# gamepad.net
KiCad netlist of a schematic drawn in EasyEDA Pro
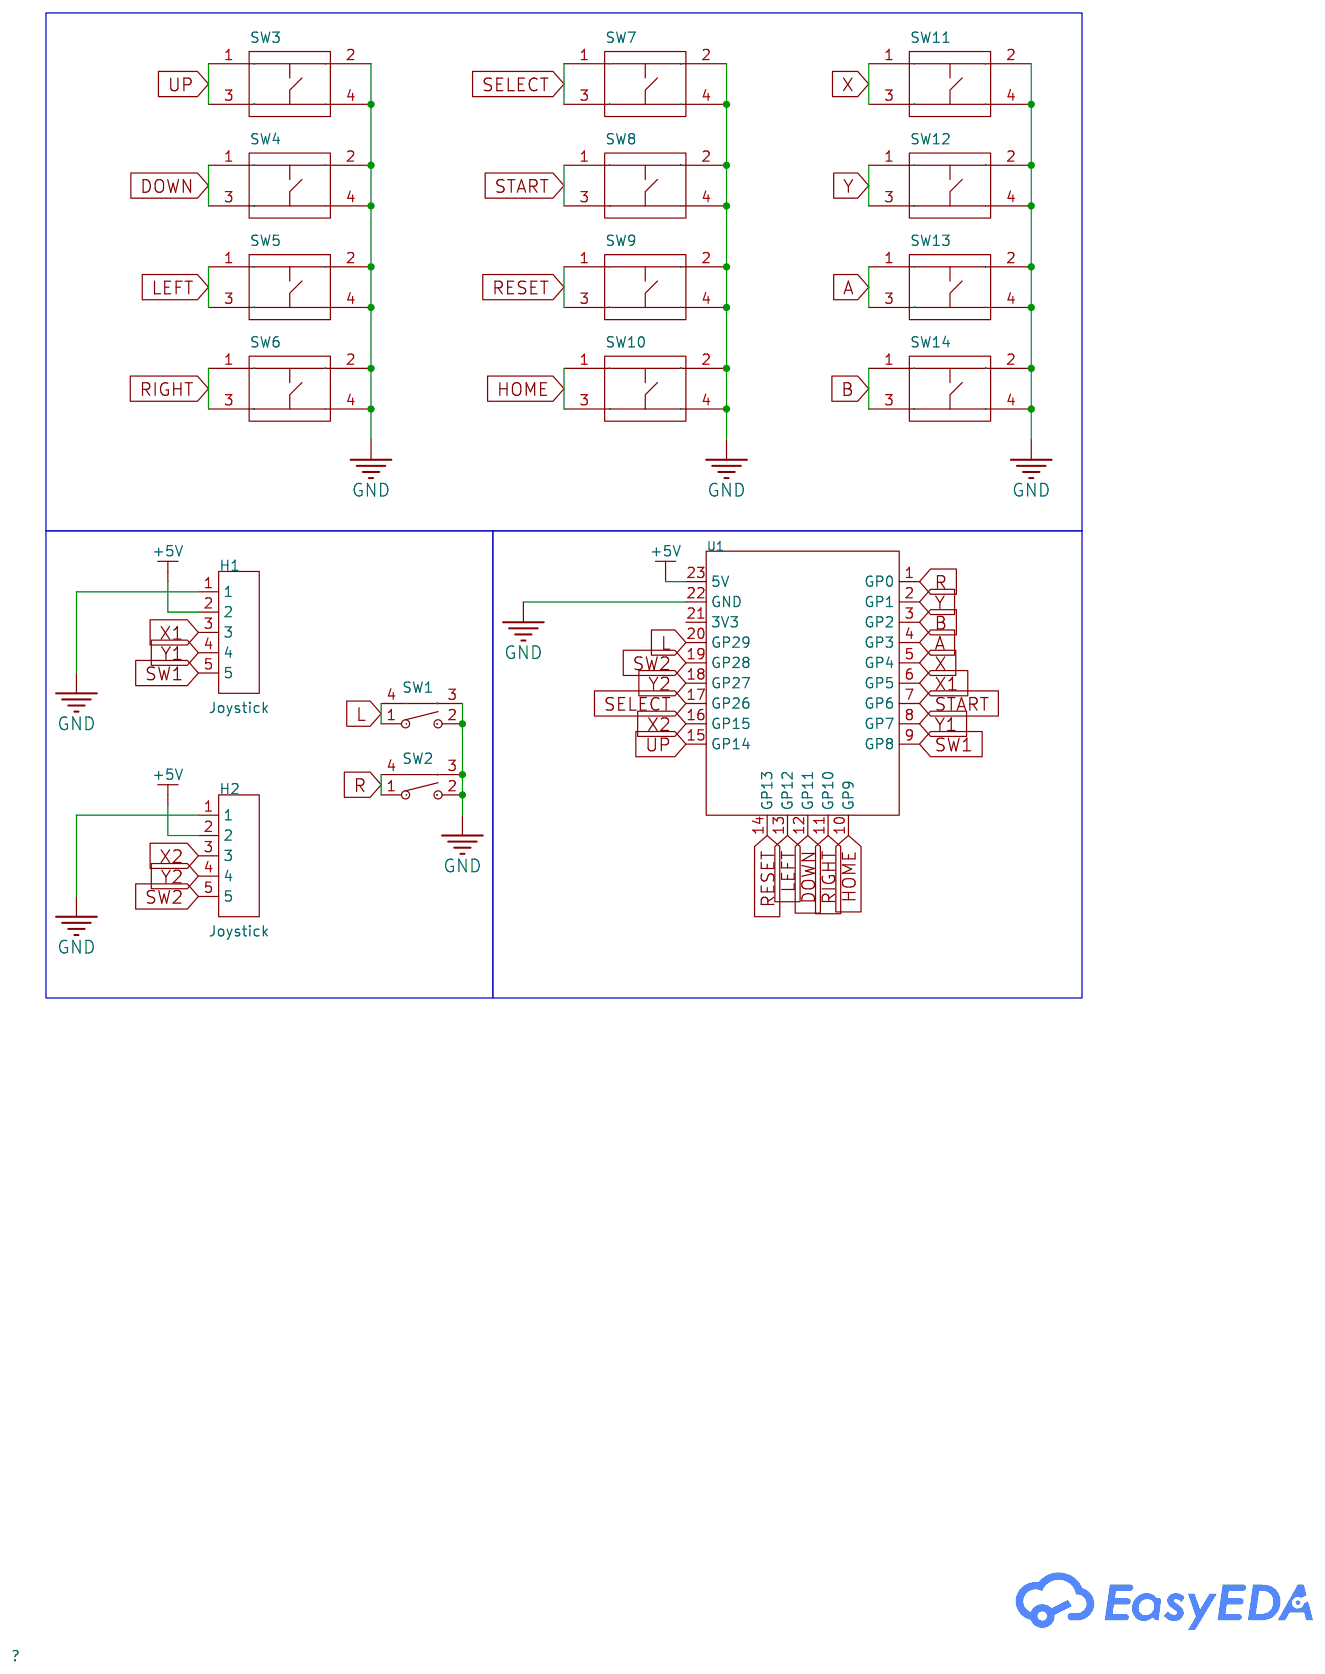
[diagram p0: schematic sheet]

(export (version "E")
  (design (tool "Eeschema 10.0.6"))
  (components
    (comp (ref "H1")
      (value "Joystick")
      (footprint "easyedapro:HDR-TH_5P-P2.54_HTSW-105-08-F-S")
      (fields (field (name "Manufacturer") "SAMTEC"))
      (libsource (lib "easyedapro") (part "MTSW-105-22-F-S-370"))
    )
    (comp (ref "H2")
      (value "Joystick")
      (footprint "easyedapro:HDR-TH_5P-P2.54_HTSW-105-08-F-S")
      (fields (field (name "Manufacturer") "SAMTEC"))
      (libsource (lib "easyedapro") (part "MTSW-105-22-F-S-370"))
    )
    (comp (ref "SW1")
      (value "K2-1102AQ-H4CW-01")
      (footprint "easyedapro:SW-TH_K2-1102BQ-G4CW-01")
      (fields (field (name "Manufacturer") "韩国韩荣"))
      (libsource (lib "easyedapro") (part "K2-1102AQ-H4CW-01"))
    )
    (comp (ref "SW2")
      (value "K2-1102AQ-H4CW-01")
      (footprint "easyedapro:SW-TH_K2-1102BQ-G4CW-01")
      (fields (field (name "Manufacturer") "韩国韩荣"))
      (libsource (lib "easyedapro") (part "K2-1102AQ-H4CW-01"))
    )
    (comp (ref "SW3")
      (value "K2-1102DP-C4SW-04")
      (footprint "easyedapro:KEY-TH_4P-L6.0-W6.0-P4.50-LS6.50")
      (fields (field (name "Manufacturer") "韩国韩荣"))
      (libsource (lib "easyedapro") (part "K2-1102DP-C4SW-04"))
    )
    (comp (ref "SW4")
      (value "K2-1102DP-C4SW-04")
      (footprint "easyedapro:KEY-TH_4P-L6.0-W6.0-P4.50-LS6.50")
      (fields (field (name "Manufacturer") "韩国韩荣"))
      (libsource (lib "easyedapro") (part "K2-1102DP-C4SW-04"))
    )
    (comp (ref "SW5")
      (value "K2-1102DP-C4SW-04")
      (footprint "easyedapro:KEY-TH_4P-L6.0-W6.0-P4.50-LS6.50")
      (fields (field (name "Manufacturer") "韩国韩荣"))
      (libsource (lib "easyedapro") (part "K2-1102DP-C4SW-04"))
    )
    (comp (ref "SW6")
      (value "K2-1102DP-C4SW-04")
      (footprint "easyedapro:KEY-TH_4P-L6.0-W6.0-P4.50-LS6.50")
      (fields (field (name "Manufacturer") "韩国韩荣"))
      (libsource (lib "easyedapro") (part "K2-1102DP-C4SW-04"))
    )
    (comp (ref "SW7")
      (value "K2-1102DP-C4SW-04")
      (footprint "easyedapro:KEY-TH_4P-L6.0-W6.0-P4.50-LS6.50")
      (fields (field (name "Manufacturer") "韩国韩荣"))
      (libsource (lib "easyedapro") (part "K2-1102DP-C4SW-04"))
    )
    (comp (ref "SW8")
      (value "K2-1102DP-C4SW-04")
      (footprint "easyedapro:KEY-TH_4P-L6.0-W6.0-P4.50-LS6.50")
      (fields (field (name "Manufacturer") "韩国韩荣"))
      (libsource (lib "easyedapro") (part "K2-1102DP-C4SW-04"))
    )
    (comp (ref "SW9")
      (value "K2-1102DP-C4SW-04")
      (footprint "easyedapro:KEY-TH_4P-L6.0-W6.0-P4.50-LS6.50")
      (fields (field (name "Manufacturer") "韩国韩荣"))
      (libsource (lib "easyedapro") (part "K2-1102DP-C4SW-04"))
    )
    (comp (ref "SW10")
      (value "K2-1102DP-C4SW-04")
      (footprint "easyedapro:KEY-TH_4P-L6.0-W6.0-P4.50-LS6.50")
      (fields (field (name "Manufacturer") "韩国韩荣"))
      (libsource (lib "easyedapro") (part "K2-1102DP-C4SW-04"))
    )
    (comp (ref "SW11")
      (value "K2-1102DP-C4SW-04")
      (footprint "easyedapro:KEY-TH_4P-L6.0-W6.0-P4.50-LS6.50")
      (fields (field (name "Manufacturer") "韩国韩荣"))
      (libsource (lib "easyedapro") (part "K2-1102DP-C4SW-04"))
    )
    (comp (ref "SW12")
      (value "K2-1102DP-C4SW-04")
      (footprint "easyedapro:KEY-TH_4P-L6.0-W6.0-P4.50-LS6.50")
      (fields (field (name "Manufacturer") "韩国韩荣"))
      (libsource (lib "easyedapro") (part "K2-1102DP-C4SW-04"))
    )
    (comp (ref "SW13")
      (value "K2-1102DP-C4SW-04")
      (footprint "easyedapro:KEY-TH_4P-L6.0-W6.0-P4.50-LS6.50")
      (fields (field (name "Manufacturer") "韩国韩荣"))
      (libsource (lib "easyedapro") (part "K2-1102DP-C4SW-04"))
    )
    (comp (ref "SW14")
      (value "K2-1102DP-C4SW-04")
      (footprint "easyedapro:KEY-TH_4P-L6.0-W6.0-P4.50-LS6.50")
      (fields (field (name "Manufacturer") "韩国韩荣"))
      (libsource (lib "easyedapro") (part "K2-1102DP-C4SW-04"))
    )
    (comp (ref "U1")
      (value "RP2040-Zero")
      (footprint "easyedapro:RP2040_Zero")
      (fields (field (name "Manufacturer") "Waveshare(微雪电子)"))
      (libsource (lib "easyedapro") (part "RP2040-ZERO"))
    )
  )
  (nets
    (net (code "1") (name "+5V") (class "Default")
      (node (ref "H1") (pin "2") (pinfunction "2_2") (pintype "unspecified"))
      (node (ref "H2") (pin "2") (pinfunction "2_2") (pintype "unspecified"))
      (node (ref "U1") (pin "23") (pinfunction "5V_23") (pintype "input"))
    )
    (net (code "2") (name "A") (class "Default")
      (node (ref "SW13") (pin "1") (pinfunction "1_1") (pintype "unspecified"))
      (node (ref "SW13") (pin "3") (pinfunction "3_3") (pintype "unspecified"))
      (node (ref "U1") (pin "4") (pinfunction "GP3_4") (pintype "input"))
    )
    (net (code "3") (name "B") (class "Default")
      (node (ref "SW14") (pin "1") (pinfunction "1_1") (pintype "unspecified"))
      (node (ref "SW14") (pin "3") (pinfunction "3_3") (pintype "unspecified"))
      (node (ref "U1") (pin "3") (pinfunction "GP2_3") (pintype "input"))
    )
    (net (code "4") (name "DOWN") (class "Default")
      (node (ref "SW4") (pin "1") (pinfunction "1_1") (pintype "unspecified"))
      (node (ref "SW4") (pin "3") (pinfunction "3_3") (pintype "unspecified"))
      (node (ref "U1") (pin "12") (pinfunction "GP11_12") (pintype "input"))
    )
    (net (code "5") (name "GND") (class "Default")
      (node (ref "H1") (pin "1") (pinfunction "1_1") (pintype "unspecified"))
      (node (ref "H2") (pin "1") (pinfunction "1_1") (pintype "unspecified"))
      (node (ref "SW1") (pin "2") (pinfunction "2_2") (pintype "input"))
      (node (ref "SW1") (pin "3") (pinfunction "3_3") (pintype "input"))
      (node (ref "SW10") (pin "2") (pinfunction "2_2") (pintype "unspecified"))
      (node (ref "SW10") (pin "4") (pinfunction "4_4") (pintype "unspecified"))
      (node (ref "SW11") (pin "2") (pinfunction "2_2") (pintype "unspecified"))
      (node (ref "SW11") (pin "4") (pinfunction "4_4") (pintype "unspecified"))
      (node (ref "SW12") (pin "2") (pinfunction "2_2") (pintype "unspecified"))
      (node (ref "SW12") (pin "4") (pinfunction "4_4") (pintype "unspecified"))
      (node (ref "SW13") (pin "2") (pinfunction "2_2") (pintype "unspecified"))
      (node (ref "SW13") (pin "4") (pinfunction "4_4") (pintype "unspecified"))
      (node (ref "SW14") (pin "2") (pinfunction "2_2") (pintype "unspecified"))
      (node (ref "SW14") (pin "4") (pinfunction "4_4") (pintype "unspecified"))
      (node (ref "SW2") (pin "2") (pinfunction "2_2") (pintype "input"))
      (node (ref "SW2") (pin "3") (pinfunction "3_3") (pintype "input"))
      (node (ref "SW3") (pin "2") (pinfunction "2_2") (pintype "unspecified"))
      (node (ref "SW3") (pin "4") (pinfunction "4_4") (pintype "unspecified"))
      (node (ref "SW4") (pin "2") (pinfunction "2_2") (pintype "unspecified"))
      (node (ref "SW4") (pin "4") (pinfunction "4_4") (pintype "unspecified"))
      (node (ref "SW5") (pin "2") (pinfunction "2_2") (pintype "unspecified"))
      (node (ref "SW5") (pin "4") (pinfunction "4_4") (pintype "unspecified"))
      (node (ref "SW6") (pin "2") (pinfunction "2_2") (pintype "unspecified"))
      (node (ref "SW6") (pin "4") (pinfunction "4_4") (pintype "unspecified"))
      (node (ref "SW7") (pin "2") (pinfunction "2_2") (pintype "unspecified"))
      (node (ref "SW7") (pin "4") (pinfunction "4_4") (pintype "unspecified"))
      (node (ref "SW8") (pin "2") (pinfunction "2_2") (pintype "unspecified"))
      (node (ref "SW8") (pin "4") (pinfunction "4_4") (pintype "unspecified"))
      (node (ref "SW9") (pin "2") (pinfunction "2_2") (pintype "unspecified"))
      (node (ref "SW9") (pin "4") (pinfunction "4_4") (pintype "unspecified"))
      (node (ref "U1") (pin "22") (pinfunction "GND_22") (pintype "input"))
    )
    (net (code "6") (name "HOME") (class "Default")
      (node (ref "SW10") (pin "1") (pinfunction "1_1") (pintype "unspecified"))
      (node (ref "SW10") (pin "3") (pinfunction "3_3") (pintype "unspecified"))
      (node (ref "U1") (pin "10") (pinfunction "GP9_10") (pintype "input"))
    )
    (net (code "7") (name "L") (class "Default")
      (node (ref "SW1") (pin "1") (pinfunction "1_1") (pintype "input"))
      (node (ref "SW1") (pin "4") (pinfunction "4_4") (pintype "input"))
      (node (ref "U1") (pin "20") (pinfunction "GP29_20") (pintype "input"))
    )
    (net (code "8") (name "LEFT") (class "Default")
      (node (ref "SW5") (pin "1") (pinfunction "1_1") (pintype "unspecified"))
      (node (ref "SW5") (pin "3") (pinfunction "3_3") (pintype "unspecified"))
      (node (ref "U1") (pin "13") (pinfunction "GP12_13") (pintype "input"))
    )
    (net (code "9") (name "R") (class "Default")
      (node (ref "SW2") (pin "1") (pinfunction "1_1") (pintype "input"))
      (node (ref "SW2") (pin "4") (pinfunction "4_4") (pintype "input"))
      (node (ref "U1") (pin "1") (pinfunction "GP0_1") (pintype "input"))
    )
    (net (code "10") (name "RESET") (class "Default")
      (node (ref "SW9") (pin "1") (pinfunction "1_1") (pintype "unspecified"))
      (node (ref "SW9") (pin "3") (pinfunction "3_3") (pintype "unspecified"))
      (node (ref "U1") (pin "14") (pinfunction "GP13_14") (pintype "input"))
    )
    (net (code "11") (name "RIGHT") (class "Default")
      (node (ref "SW6") (pin "1") (pinfunction "1_1") (pintype "unspecified"))
      (node (ref "SW6") (pin "3") (pinfunction "3_3") (pintype "unspecified"))
      (node (ref "U1") (pin "11") (pinfunction "GP10_11") (pintype "input"))
    )
    (net (code "12") (name "SELECT") (class "Default")
      (node (ref "SW7") (pin "1") (pinfunction "1_1") (pintype "unspecified"))
      (node (ref "SW7") (pin "3") (pinfunction "3_3") (pintype "unspecified"))
      (node (ref "U1") (pin "17") (pinfunction "GP26_17") (pintype "input"))
    )
    (net (code "13") (name "START") (class "Default")
      (node (ref "SW8") (pin "1") (pinfunction "1_1") (pintype "unspecified"))
      (node (ref "SW8") (pin "3") (pinfunction "3_3") (pintype "unspecified"))
      (node (ref "U1") (pin "7") (pinfunction "GP6_7") (pintype "input"))
    )
    (net (code "14") (name "SW1") (class "Default")
      (node (ref "H1") (pin "5") (pinfunction "5_5") (pintype "unspecified"))
      (node (ref "U1") (pin "9") (pinfunction "GP8_9") (pintype "input"))
    )
    (net (code "15") (name "SW2") (class "Default")
      (node (ref "H2") (pin "5") (pinfunction "5_5") (pintype "unspecified"))
      (node (ref "U1") (pin "19") (pinfunction "GP28_19") (pintype "input"))
    )
    (net (code "16") (name "UP") (class "Default")
      (node (ref "SW3") (pin "1") (pinfunction "1_1") (pintype "unspecified"))
      (node (ref "SW3") (pin "3") (pinfunction "3_3") (pintype "unspecified"))
      (node (ref "U1") (pin "15") (pinfunction "GP14_15") (pintype "input"))
    )
    (net (code "17") (name "X") (class "Default")
      (node (ref "SW11") (pin "1") (pinfunction "1_1") (pintype "unspecified"))
      (node (ref "SW11") (pin "3") (pinfunction "3_3") (pintype "unspecified"))
      (node (ref "U1") (pin "5") (pinfunction "GP4_5") (pintype "input"))
    )
    (net (code "18") (name "X1") (class "Default")
      (node (ref "H1") (pin "3") (pinfunction "3_3") (pintype "unspecified"))
      (node (ref "U1") (pin "6") (pinfunction "GP5_6") (pintype "input"))
    )
    (net (code "19") (name "X2") (class "Default")
      (node (ref "H2") (pin "3") (pinfunction "3_3") (pintype "unspecified"))
      (node (ref "U1") (pin "16") (pinfunction "GP15_16") (pintype "input"))
    )
    (net (code "20") (name "Y") (class "Default")
      (node (ref "SW12") (pin "1") (pinfunction "1_1") (pintype "unspecified"))
      (node (ref "SW12") (pin "3") (pinfunction "3_3") (pintype "unspecified"))
      (node (ref "U1") (pin "2") (pinfunction "GP1_2") (pintype "input"))
    )
    (net (code "21") (name "Y1") (class "Default")
      (node (ref "H1") (pin "4") (pinfunction "4_4") (pintype "unspecified"))
      (node (ref "U1") (pin "8") (pinfunction "GP7_8") (pintype "input"))
    )
    (net (code "22") (name "Y2") (class "Default")
      (node (ref "H2") (pin "4") (pinfunction "4_4") (pintype "unspecified"))
      (node (ref "U1") (pin "18") (pinfunction "GP27_18") (pintype "input"))
    )
    (net (code "23") (name "unconnected-(U1-3V3-Pad21)") (class "Default")
      (node (ref "U1") (pin "21") (pinfunction "3V3_21") (pintype "input"))
    )
  )
)
